# eps_power.net
KiCad netlist of a schematic drawn in Altium Designer
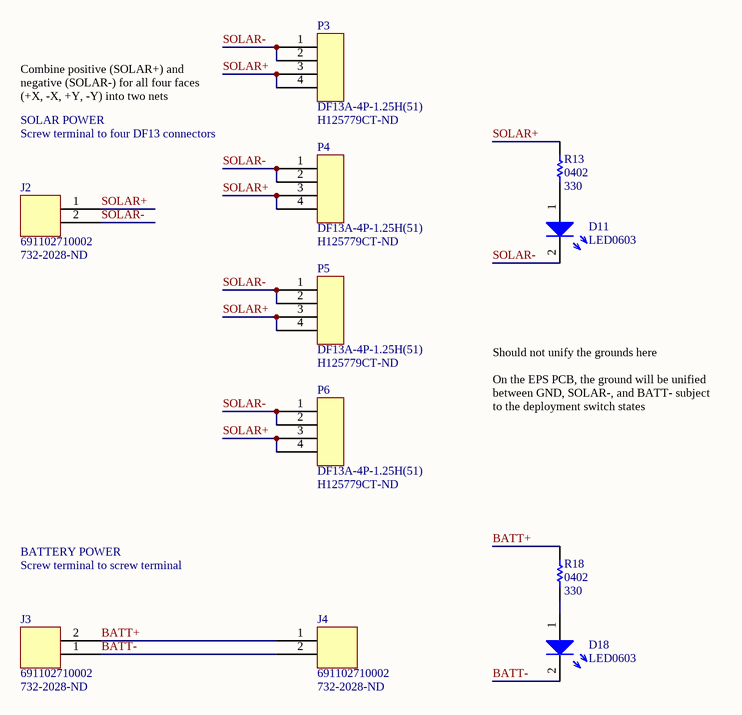
[diagram p0: eps_power.SchDoc]

(export (version "E")
  (design (tool "Eeschema 10.0.6"))
  (components
    (comp (ref "D11")
      (value "LED0603")
      (footprint "LED0603")
      (description "Generic 0603 LED. Use ChipLED from Osram for generic ones.")
      (libsource (lib "heron-general") (part "LED0603"))
    )
    (comp (ref "D18")
      (value "LED0603")
      (footprint "LED0603")
      (description "Generic 0603 LED. Use ChipLED from Osram for generic ones.")
      (libsource (lib "heron-general") (part "LED0603"))
    )
    (comp (ref "J2")
      (value "691102710002")
      (footprint "CON2_SCREW_5.00MM_691102710002")
      (description "2-POS screw terminal, 5mm pitch")
      (fields (field (name "SUPPLIER PART NUMBER 1") "732-2028-ND"))
      (libsource (lib "") (part "691102710002_2"))
    )
    (comp (ref "J3")
      (value "691102710002")
      (footprint "CON2_SCREW_5.00MM_691102710002")
      (description "2-POS screw terminal, 5mm pitch")
      (fields (field (name "SUPPLIER PART NUMBER 1") "732-2028-ND"))
      (libsource (lib "heron-general") (part "691102710002"))
    )
    (comp (ref "J4")
      (value "691102710002")
      (footprint "CON2_SCREW_5.00MM_691102710002")
      (description "2-POS screw terminal, 5mm pitch")
      (fields (field (name "SUPPLIER PART NUMBER 1") "732-2028-ND"))
      (libsource (lib "") (part "691102710002_1"))
    )
    (comp (ref "P3")
      (value "DF13A-4P-1.25H(51)")
      (footprint "DF13A-4P-1.25H(51)")
      (description "4 pos DF13 right angle surface mount connector")
      (fields (field (name "SUPPLIER PART NUMBER 1") "H125779CT-ND"))
      (libsource (lib "heron-general") (part "DF13A-4P-1.25H(51)"))
    )
    (comp (ref "P4")
      (value "DF13A-4P-1.25H(51)")
      (footprint "DF13A-4P-1.25H(51)")
      (description "4 pos DF13 right angle surface mount connector")
      (fields (field (name "SUPPLIER PART NUMBER 1") "H125779CT-ND"))
      (libsource (lib "heron-general") (part "DF13A-4P-1.25H(51)"))
    )
    (comp (ref "P5")
      (value "DF13A-4P-1.25H(51)")
      (footprint "DF13A-4P-1.25H(51)")
      (description "4 pos DF13 right angle surface mount connector")
      (fields (field (name "SUPPLIER PART NUMBER 1") "H125779CT-ND"))
      (libsource (lib "heron-general") (part "DF13A-4P-1.25H(51)"))
    )
    (comp (ref "P6")
      (value "DF13A-4P-1.25H(51)")
      (footprint "DF13A-4P-1.25H(51)")
      (description "4 pos DF13 right angle surface mount connector")
      (fields (field (name "SUPPLIER PART NUMBER 1") "H125779CT-ND"))
      (libsource (lib "heron-general") (part "DF13A-4P-1.25H(51)"))
    )
    (comp (ref "R13")
      (value "0402")
      (footprint "RES0402R")
      (description "0402 resistor")
      (fields (field (name "ALTIUM_VALUE") "330"))
      (libsource (lib "heron-general") (part "RES0402"))
    )
    (comp (ref "R18")
      (value "0402")
      (footprint "RES0402R")
      (description "0402 resistor")
      (fields (field (name "ALTIUM_VALUE") "330"))
      (libsource (lib "heron-general") (part "RES0402"))
    )
  )
  (nets
    (net (code "1") (name "/BATT+") (class "Default")
      (node (ref "J3") (pin "2") (pinfunction "2_2") (pintype "passive"))
      (node (ref "J4") (pin "1") (pinfunction "1_1") (pintype "passive"))
      (node (ref "R18") (pin "2") (pinfunction "2_2") (pintype "passive"))
    )
    (net (code "2") (name "/BATT-") (class "Default")
      (node (ref "D18") (pin "2") (pinfunction "2_2") (pintype "passive"))
      (node (ref "J3") (pin "1") (pinfunction "1_1") (pintype "passive"))
      (node (ref "J4") (pin "2") (pinfunction "2_2") (pintype "passive"))
    )
    (net (code "3") (name "/SOLAR+") (class "Default")
      (node (ref "J2") (pin "1") (pinfunction "1_1") (pintype "passive"))
      (node (ref "P3") (pin "3") (pintype "passive"))
      (node (ref "P3") (pin "4") (pintype "passive"))
      (node (ref "P4") (pin "3") (pintype "passive"))
      (node (ref "P4") (pin "4") (pintype "passive"))
      (node (ref "P5") (pin "3") (pintype "passive"))
      (node (ref "P5") (pin "4") (pintype "passive"))
      (node (ref "P6") (pin "3") (pintype "passive"))
      (node (ref "P6") (pin "4") (pintype "passive"))
      (node (ref "R13") (pin "1") (pinfunction "1_1") (pintype "passive"))
    )
    (net (code "4") (name "/SOLAR-") (class "Default")
      (node (ref "D11") (pin "2") (pinfunction "2_2") (pintype "passive"))
      (node (ref "J2") (pin "2") (pinfunction "2_2") (pintype "passive"))
      (node (ref "P3") (pin "1") (pintype "passive"))
      (node (ref "P3") (pin "2") (pintype "passive"))
      (node (ref "P4") (pin "1") (pintype "passive"))
      (node (ref "P4") (pin "2") (pintype "passive"))
      (node (ref "P5") (pin "1") (pintype "passive"))
      (node (ref "P5") (pin "2") (pintype "passive"))
      (node (ref "P6") (pin "1") (pintype "passive"))
      (node (ref "P6") (pin "2") (pintype "passive"))
    )
    (net (code "5") (name "Net-(D11-Pad1)") (class "Default")
      (node (ref "D11") (pin "1") (pinfunction "1_1") (pintype "passive"))
      (node (ref "R13") (pin "2") (pinfunction "2_2") (pintype "passive"))
    )
    (net (code "6") (name "Net-(D18-Pad1)") (class "Default")
      (node (ref "D18") (pin "1") (pinfunction "1_1") (pintype "passive"))
      (node (ref "R18") (pin "1") (pinfunction "1_1") (pintype "passive"))
    )
  )
)
